# 5_Auto_Reset.net
KiCad netlist of a schematic drawn in Altium Designer
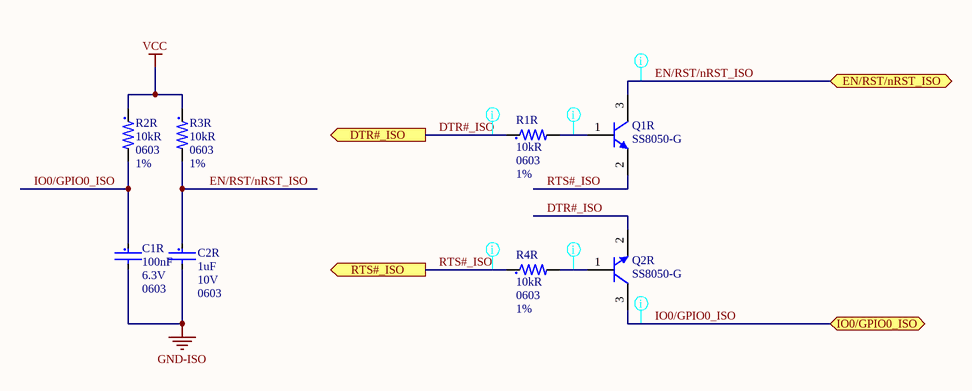
[diagram p0: 5_Auto_Reset.SchDoc]

(export (version "E")
  (design (tool "Eeschema 10.0.6"))
  (components
    (comp (ref "C1R")
      (value "100nF")
      (footprint "C0603-IPC_C_No_Silk")
      (description "Cap Cer 0.1UF 6.3V X7R 0603")
      (fields
        (field (name "MANUFACTURER") "KYOCERA AVX")
        (field (name "MANUFACTURER PART NUMBER") "KGM15AR70J104KM")
        (field (name "VOLTAGE") "6.3V")
        (field (name "PACKAGE") "0603")
      )
      (libsource (lib "Lib_Capacitor_0603") (part "100nF_6.3V"))
    )
    (comp (ref "C2R")
      (value "1uF")
      (footprint "C0603-IPC_C_No_Silk")
      (description "Ceramic Capacitor, Multilayer, Ceramic, 10V, 10% +Tol, 10% -Tol, X5R, 15% TC, 1uF, 0603")
      (fields
        (field (name "MANUFACTURER") "KEMET")
        (field (name "MANUFACTURER PART NUMBER") "C0603C105K8PACTU")
        (field (name "VOLTAGE RATING") "10V")
        (field (name "CASE CODE (IMPERIAL)") "0603")
      )
      (libsource (lib "Lib_Capacitor_0603") (part "1uF_10V"))
    )
    (comp (ref "Q1R")
      (value "SS8050-G")
      (footprint "SOT-23-3-MFG")
      (description "Trans Gp Bjt NPN 25V 1.5A 300MW 3-PIN SOT-23 T/r")
      (fields (field (name "MANUFACTURER") "Comchip"))
      (libsource (lib "Lib_Transistor_NPN") (part "SS8050-G"))
    )
    (comp (ref "Q2R")
      (value "SS8050-G")
      (footprint "SOT-23-3-MFG")
      (description "Trans Gp Bjt NPN 25V 1.5A 300MW 3-PIN SOT-23 T/r")
      (fields (field (name "MANUFACTURER") "Comchip"))
      (libsource (lib "Lib_Transistor_NPN") (part "SS8050-G"))
    )
    (comp (ref "R1R")
      (value "10kR")
      (footprint "R0603-MFG")
      (description "SMD Chip Resistor, 10 kOhm, ± 1%, 100 mW, 0603 [1608 Metric], Thick Film, General Purpose")
      (fields
        (field (name "MANUFACTURER") "Yageo")
        (field (name "MANUFACTURER PART NUMBER") "RC0603FR-0710KL")
        (field (name "CASE/PACKAGE") "0603")
        (field (name "TOLERANCE") "1%")
      )
      (libsource (lib "") (part "10K_1"))
    )
    (comp (ref "R2R")
      (value "10kR")
      (footprint "R0603-MFG")
      (description "SMD Chip Resistor, 10 kOhm, ± 1%, 100 mW, 0603 [1608 Metric], Thick Film, General Purpose")
      (fields
        (field (name "MANUFACTURER") "Yageo")
        (field (name "MANUFACTURER PART NUMBER") "RC0603FR-0710KL")
        (field (name "CASE/PACKAGE") "0603")
        (field (name "TOLERANCE") "1%")
      )
      (libsource (lib "Lib_Register_0603") (part "10K"))
    )
    (comp (ref "R3R")
      (value "10kR")
      (footprint "R0603-MFG")
      (description "SMD Chip Resistor, 10 kOhm, ± 1%, 100 mW, 0603 [1608 Metric], Thick Film, General Purpose")
      (fields
        (field (name "MANUFACTURER") "Yageo")
        (field (name "MANUFACTURER PART NUMBER") "RC0603FR-0710KL")
        (field (name "CASE/PACKAGE") "0603")
        (field (name "TOLERANCE") "1%")
      )
      (libsource (lib "Lib_Register_0603") (part "10K"))
    )
    (comp (ref "R4R")
      (value "10kR")
      (footprint "R0603-MFG")
      (description "SMD Chip Resistor, 10 kOhm, ± 1%, 100 mW, 0603 [1608 Metric], Thick Film, General Purpose")
      (fields
        (field (name "MANUFACTURER") "Yageo")
        (field (name "MANUFACTURER PART NUMBER") "RC0603FR-0710KL")
        (field (name "CASE/PACKAGE") "0603")
        (field (name "TOLERANCE") "1%")
      )
      (libsource (lib "") (part "10K_1"))
    )
  )
  (nets
    (net (code "1") (name "/DTR#_ISO") (class "Default")
      (node (ref "Q2R") (pin "2") (pinfunction "E_2") (pintype "passive"))
      (node (ref "R1R") (pin "1") (pinfunction "1_1") (pintype "passive"))
    )
    (net (code "2") (name "/EN{slash}RST{slash}nRST_ISO") (class "Default")
      (node (ref "C2R") (pin "1") (pinfunction "1_1") (pintype "passive"))
      (node (ref "Q1R") (pin "3") (pinfunction "C_3") (pintype "passive"))
      (node (ref "R3R") (pin "2") (pinfunction "2_2") (pintype "passive"))
    )
    (net (code "3") (name "/IO0{slash}GPIO0_ISO") (class "Default")
      (node (ref "C1R") (pin "1") (pinfunction "1_1") (pintype "passive"))
      (node (ref "Q2R") (pin "3") (pinfunction "C_3") (pintype "passive"))
      (node (ref "R2R") (pin "2") (pinfunction "2_2") (pintype "passive"))
    )
    (net (code "4") (name "/RTS#_ISO") (class "Default")
      (node (ref "Q1R") (pin "2") (pinfunction "E_2") (pintype "passive"))
      (node (ref "R4R") (pin "1") (pinfunction "1_1") (pintype "passive"))
    )
    (net (code "5") (name "GND-ISO") (class "Default")
      (node (ref "C1R") (pin "2") (pinfunction "2_2") (pintype "passive"))
      (node (ref "C2R") (pin "2") (pinfunction "2_2") (pintype "passive"))
    )
    (net (code "6") (name "Net-(Q1R-B)") (class "Default")
      (node (ref "Q1R") (pin "1") (pinfunction "B_1") (pintype "passive"))
      (node (ref "R1R") (pin "2") (pinfunction "2_2") (pintype "passive"))
    )
    (net (code "7") (name "Net-(Q2R-B)") (class "Default")
      (node (ref "Q2R") (pin "1") (pinfunction "B_1") (pintype "passive"))
      (node (ref "R4R") (pin "2") (pinfunction "2_2") (pintype "passive"))
    )
    (net (code "8") (name "VCC") (class "Default")
      (node (ref "R2R") (pin "1") (pinfunction "1_1") (pintype "passive"))
      (node (ref "R3R") (pin "1") (pinfunction "1_1") (pintype "passive"))
    )
  )
)
